# Training_Board.net
KiCad netlist of a schematic drawn in EAGLE
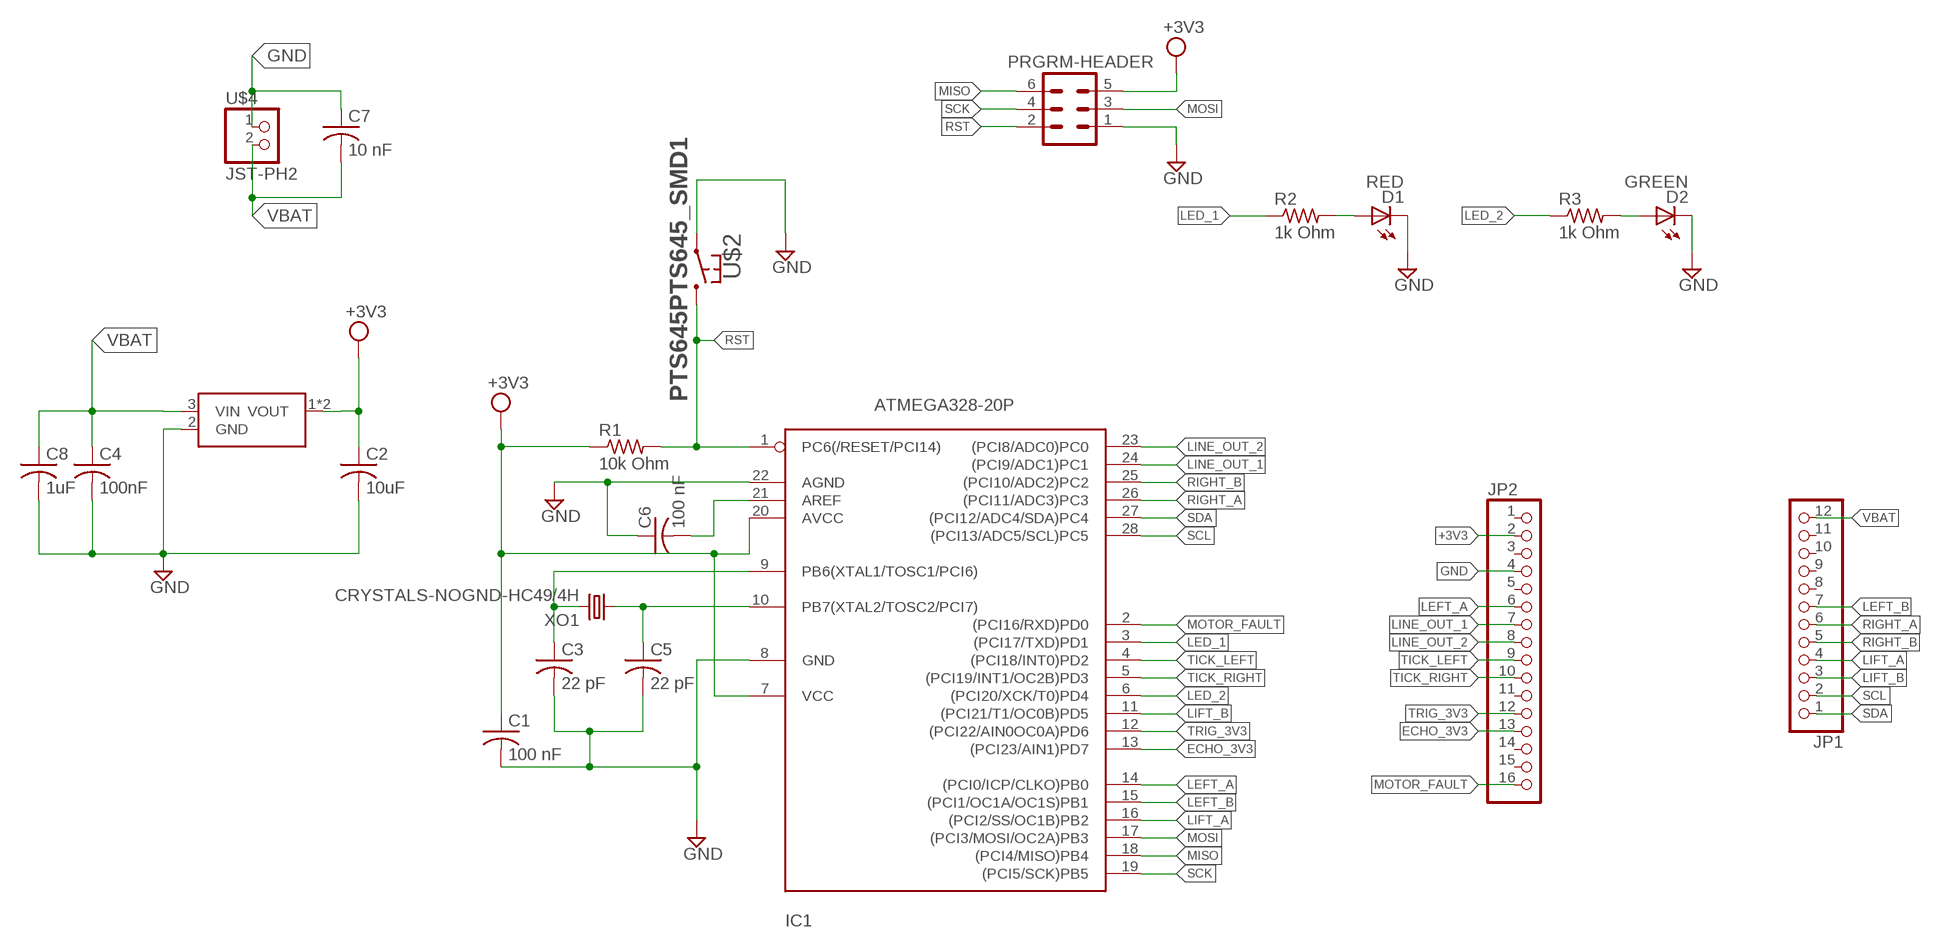
[diagram p0: schematic, sheet 1]

(export (version "E")
  (design (tool "Eeschema 10.0.6"))
  (components
    (comp (ref "C1")
      (value "100 nF")
      (footprint "eagle-import:C0603")
      (libsource (lib "eagle-import") (part "resistor_348_C-USC0603"))
    )
    (comp (ref "C2")
      (value "10uF")
      (footprint "eagle-import:C0603")
      (libsource (lib "eagle-import") (part "C-USC0603"))
    )
    (comp (ref "C3")
      (value "22 pF")
      (footprint "eagle-import:C0603")
      (libsource (lib "eagle-import") (part "resistor_348_C-USC0603"))
    )
    (comp (ref "C4")
      (value "100nF")
      (footprint "eagle-import:C0603")
      (libsource (lib "eagle-import") (part "C-USC0603"))
    )
    (comp (ref "C5")
      (value "22 pF")
      (footprint "eagle-import:C0603")
      (libsource (lib "eagle-import") (part "resistor_348_C-USC0603"))
    )
    (comp (ref "C6")
      (value "100 nF")
      (footprint "eagle-import:C0603")
      (libsource (lib "eagle-import") (part "resistor_348_C-USC0603"))
    )
    (comp (ref "C7")
      (value "10 nF")
      (footprint "eagle-import:C0603")
      (libsource (lib "eagle-import") (part "resistor_348_C-USC0603"))
    )
    (comp (ref "C8")
      (value "1uF")
      (footprint "eagle-import:C0603")
      (libsource (lib "eagle-import") (part "C-USC0603"))
    )
    (comp (ref "D1")
      (value "RED")
      (footprint "eagle-import:CHIP-LED0603")
      (libsource (lib "eagle-import") (part "LEDCHIP-LED0603"))
    )
    (comp (ref "D2")
      (value "GREEN")
      (footprint "eagle-import:CHIP-LED0603")
      (libsource (lib "eagle-import") (part "LEDCHIP-LED0603"))
    )
    (comp (ref "IC1")
      (value "ATMEGA328-20P")
      (footprint "eagle-import:DIL28-3")
      (libsource (lib "eagle-import") (part "ATMEGA328P-20"))
    )
    (comp (ref "JP1")
      (value "PINHD-1X12")
      (footprint "eagle-import:1X12")
      (libsource (lib "eagle-import") (part "PINHD-1X12"))
    )
    (comp (ref "JP2")
      (value "PINHD-1X16")
      (footprint "eagle-import:1X16")
      (libsource (lib "eagle-import") (part "PINHD-1X16"))
    )
    (comp (ref "PRGRM-HEADER")
      (value "MA03-2")
      (footprint "eagle-import:MA03-2")
      (libsource (lib "eagle-import") (part "MA03-2"))
    )
    (comp (ref "R1")
      (value "10k Ohm")
      (footprint "eagle-import:R0603")
      (libsource (lib "eagle-import") (part "R-US_R0603"))
    )
    (comp (ref "R2")
      (value "1k Ohm")
      (footprint "eagle-import:R0603")
      (libsource (lib "eagle-import") (part "R-US_R0603"))
    )
    (comp (ref "R3")
      (value "1k Ohm")
      (footprint "eagle-import:R0603")
      (libsource (lib "eagle-import") (part "R-US_R0603"))
    )
    (comp (ref "U$2")
      (value "PTS645PTS645_SMD1")
      (footprint "eagle-import:PTS645_SMD")
      (libsource (lib "eagle-import") (part "PTS645PTS645_SMD1"))
    )
    (comp (ref "U$4")
      (value "JST-PH2")
      (footprint "eagle-import:JST-PH")
      (libsource (lib "eagle-import") (part "JST-PH2"))
    )
    (comp (ref "U3")
      (value "LD1117ASOT223")
      (footprint "eagle-import:SOT230P700X180-4")
      (libsource (lib "eagle-import") (part "LD1117ASOT223"))
    )
    (comp (ref "XO1")
      (value "CRYSTALS-NOGND-HC49/4H")
      (footprint "eagle-import:HC49")
      (libsource (lib "eagle-import") (part "CRYSTALS-NOGND-HC49/4H"))
    )
  )
  (nets
    (net (code "1") (name "+3V3") (class "Default")
      (node (ref "C1") (pin "1") (pinfunction "1_1") (pintype "passive"))
      (node (ref "C2") (pin "1") (pinfunction "1_1") (pintype "passive"))
      (node (ref "IC1") (pin "20") (pinfunction "AVCC_20") (pintype "bidirectional"))
      (node (ref "IC1") (pin "7") (pinfunction "VCC_7") (pintype "bidirectional"))
      (node (ref "JP2") (pin "2") (pinfunction "2_2") (pintype "passive"))
      (node (ref "PRGRM-HEADER") (pin "5") (pinfunction "5_5") (pintype "passive"))
      (node (ref "R1") (pin "1") (pinfunction "1_1") (pintype "passive"))
      (node (ref "U3") (pin "1") (pinfunction "VOUT_1") (pintype "bidirectional"))
      (node (ref "U3") (pin "4") (pinfunction "VOUT_4") (pintype "bidirectional"))
    )
    (net (code "2") (name "ECHO_3V3") (class "Default")
      (node (ref "IC1") (pin "13") (pinfunction "(PCI23/AIN1)PD7_13") (pintype "bidirectional"))
      (node (ref "JP2") (pin "13") (pinfunction "13_13") (pintype "passive"))
    )
    (net (code "3") (name "GND") (class "Default")
      (node (ref "C1") (pin "2") (pinfunction "2_2") (pintype "passive"))
      (node (ref "C2") (pin "2") (pinfunction "2_2") (pintype "passive"))
      (node (ref "C3") (pin "2") (pinfunction "2_2") (pintype "passive"))
      (node (ref "C4") (pin "2") (pinfunction "2_2") (pintype "passive"))
      (node (ref "C5") (pin "2") (pinfunction "2_2") (pintype "passive"))
      (node (ref "C6") (pin "1") (pinfunction "1_1") (pintype "passive"))
      (node (ref "C7") (pin "1") (pinfunction "1_1") (pintype "passive"))
      (node (ref "C8") (pin "2") (pinfunction "2_2") (pintype "passive"))
      (node (ref "D1") (pin "C") (pinfunction "C_C") (pintype "passive"))
      (node (ref "D2") (pin "C") (pinfunction "C_C") (pintype "passive"))
      (node (ref "IC1") (pin "22") (pinfunction "AGND_22") (pintype "bidirectional"))
      (node (ref "IC1") (pin "8") (pinfunction "GND_8") (pintype "bidirectional"))
      (node (ref "JP2") (pin "4") (pinfunction "4_4") (pintype "passive"))
      (node (ref "PRGRM-HEADER") (pin "1") (pinfunction "1_1") (pintype "passive"))
      (node (ref "U$2") (pin "P$1") (pinfunction "1_P$1") (pintype "passive"))
      (node (ref "U$2") (pin "P$2") (pinfunction "1_P$2") (pintype "passive"))
      (node (ref "U$4") (pin "1") (pinfunction "1_1") (pintype "passive"))
      (node (ref "U3") (pin "2") (pinfunction "GND_2") (pintype "bidirectional"))
    )
    (net (code "4") (name "LED_1") (class "Default")
      (node (ref "IC1") (pin "3") (pinfunction "(PCI17/TXD)PD1_3") (pintype "bidirectional"))
      (node (ref "R2") (pin "1") (pinfunction "1_1") (pintype "passive"))
    )
    (net (code "5") (name "LED_2") (class "Default")
      (node (ref "IC1") (pin "6") (pinfunction "(PCI20/XCK/T0)PD4_6") (pintype "bidirectional"))
      (node (ref "R3") (pin "1") (pinfunction "1_1") (pintype "passive"))
    )
    (net (code "6") (name "LEFT_A") (class "Default")
      (node (ref "IC1") (pin "14") (pinfunction "(PCI0/ICP/CLKO)PB0_14") (pintype "bidirectional"))
      (node (ref "JP2") (pin "6") (pinfunction "6_6") (pintype "passive"))
    )
    (net (code "7") (name "LEFT_B") (class "Default")
      (node (ref "IC1") (pin "15") (pinfunction "(PCI1/OC1A/OC1S)PB1_15") (pintype "bidirectional"))
      (node (ref "JP1") (pin "7") (pinfunction "7_7") (pintype "passive"))
    )
    (net (code "8") (name "LIFT_A") (class "Default")
      (node (ref "IC1") (pin "16") (pinfunction "(PCI2/SS/OC1B)PB2_16") (pintype "bidirectional"))
      (node (ref "JP1") (pin "4") (pinfunction "4_4") (pintype "passive"))
    )
    (net (code "9") (name "LIFT_B") (class "Default")
      (node (ref "IC1") (pin "11") (pinfunction "(PCI21/T1/OC0B)PD5_11") (pintype "bidirectional"))
      (node (ref "JP1") (pin "3") (pinfunction "3_3") (pintype "passive"))
    )
    (net (code "10") (name "LINE_OUT_1") (class "Default")
      (node (ref "IC1") (pin "24") (pinfunction "(PCI9/ADC1)PC1_24") (pintype "bidirectional"))
      (node (ref "JP2") (pin "7") (pinfunction "7_7") (pintype "passive"))
    )
    (net (code "11") (name "LINE_OUT_2") (class "Default")
      (node (ref "IC1") (pin "23") (pinfunction "(PCI8/ADC0)PC0_23") (pintype "bidirectional"))
      (node (ref "JP2") (pin "8") (pinfunction "8_8") (pintype "passive"))
    )
    (net (code "12") (name "MISO") (class "Default")
      (node (ref "IC1") (pin "18") (pinfunction "(PCI4/MISO)PB4_18") (pintype "bidirectional"))
      (node (ref "PRGRM-HEADER") (pin "6") (pinfunction "6_6") (pintype "passive"))
    )
    (net (code "13") (name "MOSI") (class "Default")
      (node (ref "IC1") (pin "17") (pinfunction "(PCI3/MOSI/OC2A)PB3_17") (pintype "bidirectional"))
      (node (ref "PRGRM-HEADER") (pin "3") (pinfunction "3_3") (pintype "passive"))
    )
    (net (code "14") (name "MOTOR_FAULT") (class "Default")
      (node (ref "IC1") (pin "2") (pinfunction "(PCI16/RXD)PD0_2") (pintype "bidirectional"))
      (node (ref "JP2") (pin "16") (pinfunction "16_16") (pintype "passive"))
    )
    (net (code "15") (name "Net-(D1-PadA)") (class "Default")
      (node (ref "D1") (pin "A") (pinfunction "A_A") (pintype "passive"))
      (node (ref "R2") (pin "2") (pinfunction "2_2") (pintype "passive"))
    )
    (net (code "16") (name "Net-(D2-PadA)") (class "Default")
      (node (ref "D2") (pin "A") (pinfunction "A_A") (pintype "passive"))
      (node (ref "R3") (pin "2") (pinfunction "2_2") (pintype "passive"))
    )
    (net (code "17") (name "Net-(IC1-AREF)") (class "Default")
      (node (ref "C6") (pin "2") (pinfunction "2_2") (pintype "passive"))
      (node (ref "IC1") (pin "21") (pinfunction "AREF_21") (pintype "bidirectional"))
    )
    (net (code "18") (name "Net-(IC1-PB6(XTAL1{slash}TOSC1{slash}PCI6))") (class "Default")
      (node (ref "C3") (pin "1") (pinfunction "1_1") (pintype "passive"))
      (node (ref "IC1") (pin "9") (pinfunction "PB6(XTAL1/TOSC1/PCI6)_9") (pintype "bidirectional"))
      (node (ref "XO1") (pin "2") (pinfunction "2_2") (pintype "passive"))
    )
    (net (code "19") (name "Net-(IC1-PB7(XTAL2{slash}TOSC2{slash}PCI7))") (class "Default")
      (node (ref "C5") (pin "1") (pinfunction "1_1") (pintype "passive"))
      (node (ref "IC1") (pin "10") (pinfunction "PB7(XTAL2/TOSC2/PCI7)_10") (pintype "bidirectional"))
      (node (ref "XO1") (pin "1") (pinfunction "1_1") (pintype "passive"))
    )
    (net (code "20") (name "RIGHT_A") (class "Default")
      (node (ref "IC1") (pin "26") (pinfunction "(PCI11/ADC3)PC3_26") (pintype "bidirectional"))
      (node (ref "JP1") (pin "6") (pinfunction "6_6") (pintype "passive"))
    )
    (net (code "21") (name "RIGHT_B") (class "Default")
      (node (ref "IC1") (pin "25") (pinfunction "(PCI10/ADC2)PC2_25") (pintype "bidirectional"))
      (node (ref "JP1") (pin "5") (pinfunction "5_5") (pintype "passive"))
    )
    (net (code "22") (name "RST") (class "Default")
      (node (ref "IC1") (pin "1") (pinfunction "PC6(/RESET/PCI14)_1") (pintype "bidirectional"))
      (node (ref "PRGRM-HEADER") (pin "2") (pinfunction "2_2") (pintype "passive"))
      (node (ref "R1") (pin "2") (pinfunction "2_2") (pintype "passive"))
      (node (ref "U$2") (pin "P$3") (pinfunction "2_P$3") (pintype "passive"))
      (node (ref "U$2") (pin "P$4") (pinfunction "2_P$4") (pintype "passive"))
    )
    (net (code "23") (name "SCK") (class "Default")
      (node (ref "IC1") (pin "19") (pinfunction "(PCI5/SCK)PB5_19") (pintype "bidirectional"))
      (node (ref "PRGRM-HEADER") (pin "4") (pinfunction "4_4") (pintype "passive"))
    )
    (net (code "24") (name "SCL") (class "Default")
      (node (ref "IC1") (pin "28") (pinfunction "(PCI13/ADC5/SCL)PC5_28") (pintype "bidirectional"))
      (node (ref "JP1") (pin "2") (pinfunction "2_2") (pintype "passive"))
    )
    (net (code "25") (name "SDA") (class "Default")
      (node (ref "IC1") (pin "27") (pinfunction "(PCI12/ADC4/SDA)PC4_27") (pintype "bidirectional"))
      (node (ref "JP1") (pin "1") (pinfunction "1_1") (pintype "passive"))
    )
    (net (code "26") (name "TICK_LEFT") (class "Default")
      (node (ref "IC1") (pin "4") (pinfunction "(PCI18/INT0)PD2_4") (pintype "bidirectional"))
      (node (ref "JP2") (pin "9") (pinfunction "9_9") (pintype "passive"))
    )
    (net (code "27") (name "TICK_RIGHT") (class "Default")
      (node (ref "IC1") (pin "5") (pinfunction "(PCI19/INT1/OC2B)PD3_5") (pintype "bidirectional"))
      (node (ref "JP2") (pin "10") (pinfunction "10_10") (pintype "passive"))
    )
    (net (code "28") (name "TRIG_3V3") (class "Default")
      (node (ref "IC1") (pin "12") (pinfunction "(PCI22/AIN0OC0A)PD6_12") (pintype "bidirectional"))
      (node (ref "JP2") (pin "12") (pinfunction "12_12") (pintype "passive"))
    )
    (net (code "29") (name "VBAT") (class "Default")
      (node (ref "C4") (pin "1") (pinfunction "1_1") (pintype "passive"))
      (node (ref "C7") (pin "2") (pinfunction "2_2") (pintype "passive"))
      (node (ref "C8") (pin "1") (pinfunction "1_1") (pintype "passive"))
      (node (ref "JP1") (pin "12") (pinfunction "12_12") (pintype "passive"))
      (node (ref "U$4") (pin "2") (pinfunction "2_2") (pintype "passive"))
      (node (ref "U3") (pin "3") (pinfunction "VIN_3") (pintype "bidirectional"))
    )
    (net (code "30") (name "unconnected-(JP1-Pad8)") (class "Default")
      (node (ref "JP1") (pin "8") (pinfunction "8_8") (pintype "passive"))
    )
    (net (code "31") (name "unconnected-(JP1-Pad9)") (class "Default")
      (node (ref "JP1") (pin "9") (pinfunction "9_9") (pintype "passive"))
    )
    (net (code "32") (name "unconnected-(JP1-Pad10)") (class "Default")
      (node (ref "JP1") (pin "10") (pinfunction "10_10") (pintype "passive"))
    )
    (net (code "33") (name "unconnected-(JP1-Pad11)") (class "Default")
      (node (ref "JP1") (pin "11") (pinfunction "11_11") (pintype "passive"))
    )
    (net (code "34") (name "unconnected-(JP2-Pad1)") (class "Default")
      (node (ref "JP2") (pin "1") (pinfunction "1_1") (pintype "passive"))
    )
    (net (code "35") (name "unconnected-(JP2-Pad3)") (class "Default")
      (node (ref "JP2") (pin "3") (pinfunction "3_3") (pintype "passive"))
    )
    (net (code "36") (name "unconnected-(JP2-Pad5)") (class "Default")
      (node (ref "JP2") (pin "5") (pinfunction "5_5") (pintype "passive"))
    )
    (net (code "37") (name "unconnected-(JP2-Pad11)") (class "Default")
      (node (ref "JP2") (pin "11") (pinfunction "11_11") (pintype "passive"))
    )
    (net (code "38") (name "unconnected-(JP2-Pad14)") (class "Default")
      (node (ref "JP2") (pin "14") (pinfunction "14_14") (pintype "passive"))
    )
    (net (code "39") (name "unconnected-(JP2-Pad15)") (class "Default")
      (node (ref "JP2") (pin "15") (pinfunction "15_15") (pintype "passive"))
    )
  )
)
